# porta_OU_F.net
KiCad netlist of a schematic drawn in EAGLE
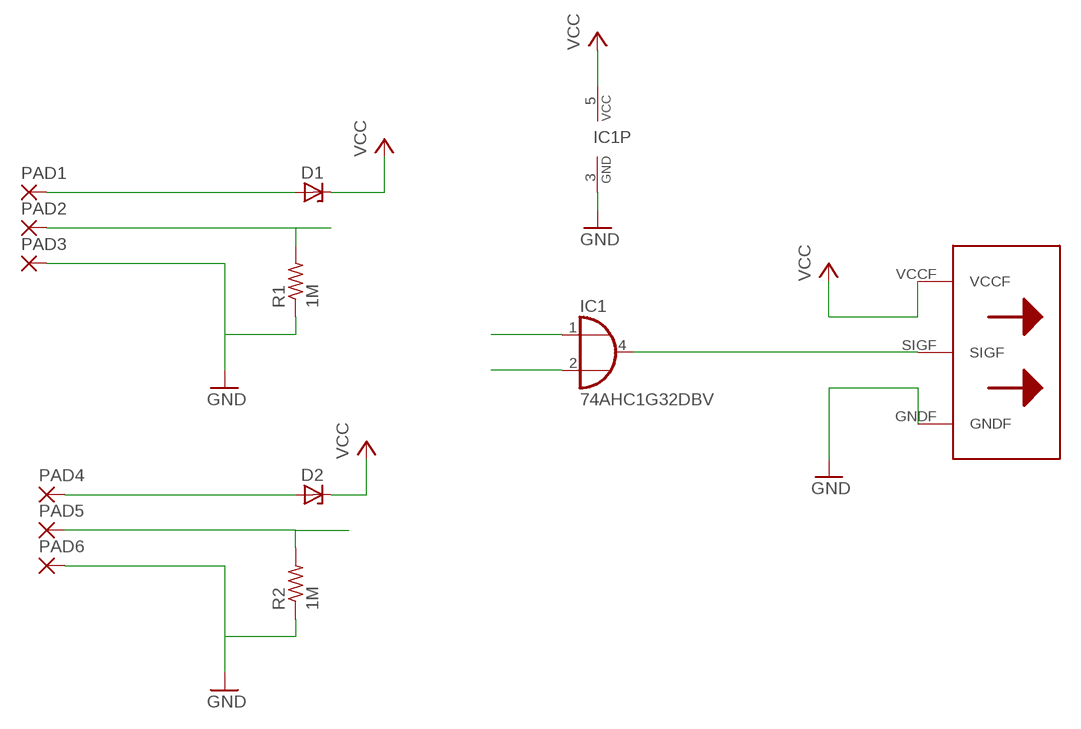
[diagram p0: schematic, sheet 1]

(export (version "E")
  (design (tool "Eeschema 10.0.6"))
  (components
    (comp (ref "D1")
      (value "ZENER-DIODESOD80C")
      (footprint "eagle-import:SOD80C")
      (libsource (lib "eagle-import") (part "ZENER-DIODESOD80C"))
    )
    (comp (ref "D2")
      (value "ZENER-DIODESOD80C")
      (footprint "eagle-import:SOD80C")
      (libsource (lib "eagle-import") (part "ZENER-DIODESOD80C"))
    )
    (comp (ref "IC1")
      (value "74AHC1G32DBV")
      (footprint "eagle-import:SOT23-5")
      (libsource (lib "eagle-import") (part "741G32DBVAHC"))
    )
    (comp (ref "PAD1")
      (value "SMD5")
      (footprint "eagle-import:SMD2,54-5,08")
      (libsource (lib "eagle-import") (part "SMD5"))
    )
    (comp (ref "PAD2")
      (value "SMD5")
      (footprint "eagle-import:SMD2,54-5,08")
      (libsource (lib "eagle-import") (part "SMD5"))
    )
    (comp (ref "PAD3")
      (value "SMD5")
      (footprint "eagle-import:SMD2,54-5,08")
      (libsource (lib "eagle-import") (part "SMD5"))
    )
    (comp (ref "PAD4")
      (value "SMD5")
      (footprint "eagle-import:SMD2,54-5,08")
      (libsource (lib "eagle-import") (part "SMD5"))
    )
    (comp (ref "PAD5")
      (value "SMD5")
      (footprint "eagle-import:SMD2,54-5,08")
      (libsource (lib "eagle-import") (part "SMD5"))
    )
    (comp (ref "PAD6")
      (value "SMD5")
      (footprint "eagle-import:SMD2,54-5,08")
      (libsource (lib "eagle-import") (part "SMD5"))
    )
    (comp (ref "R1")
      (value "1M")
      (footprint "eagle-import:M0805")
      (libsource (lib "eagle-import") (part "R-US_M0805"))
    )
    (comp (ref "R2")
      (value "1M")
      (footprint "eagle-import:M0805")
      (libsource (lib "eagle-import") (part "R-US_M0805"))
    )
    (comp (ref "U$2")
      (value "BITWIREF")
      (footprint "eagle-import:BITWIREF")
      (libsource (lib "eagle-import") (part "BITWIREF"))
    )
  )
  (nets
    (net (code "1") (name "/SIG1") (class "Default")
      (node (ref "IC1") (pin "1") (pinfunction "I0_1") (pintype "input"))
      (node (ref "PAD2") (pin "1") (pinfunction "P_1") (pintype "passive"))
      (node (ref "R1") (pin "2") (pinfunction "2_2") (pintype "passive"))
    )
    (net (code "2") (name "/SIG2") (class "Default")
      (node (ref "IC1") (pin "2") (pinfunction "I1_2") (pintype "input"))
      (node (ref "PAD5") (pin "1") (pinfunction "P_1") (pintype "passive"))
      (node (ref "R2") (pin "2") (pinfunction "2_2") (pintype "passive"))
    )
    (net (code "3") (name "GND") (class "Default")
      (node (ref "IC1") (pin "3") (pinfunction "GND_3") (pintype "power_in"))
      (node (ref "PAD3") (pin "1") (pinfunction "P_1") (pintype "passive"))
      (node (ref "PAD6") (pin "1") (pinfunction "P_1") (pintype "passive"))
      (node (ref "R1") (pin "1") (pinfunction "1_1") (pintype "passive"))
      (node (ref "R2") (pin "1") (pinfunction "1_1") (pintype "passive"))
      (node (ref "U$2") (pin "GNDF") (pinfunction "GNDF_GNDF") (pintype "bidirectional"))
    )
    (net (code "4") (name "Net-(IC1A-O)") (class "Default")
      (node (ref "IC1") (pin "4") (pinfunction "O_4") (pintype "output"))
      (node (ref "U$2") (pin "SIGF") (pinfunction "SIGF_SIGF") (pintype "bidirectional"))
    )
    (net (code "5") (name "Net-(PAD1-P)") (class "Default")
      (node (ref "D1") (pin "A") (pinfunction "A_A") (pintype "passive"))
      (node (ref "PAD1") (pin "1") (pinfunction "P_1") (pintype "passive"))
    )
    (net (code "6") (name "Net-(PAD4-P)") (class "Default")
      (node (ref "D2") (pin "A") (pinfunction "A_A") (pintype "passive"))
      (node (ref "PAD4") (pin "1") (pinfunction "P_1") (pintype "passive"))
    )
    (net (code "7") (name "VCC") (class "Default")
      (node (ref "D1") (pin "C") (pinfunction "C_C") (pintype "passive"))
      (node (ref "D2") (pin "C") (pinfunction "C_C") (pintype "passive"))
      (node (ref "IC1") (pin "5") (pinfunction "VCC_5") (pintype "power_in"))
      (node (ref "U$2") (pin "VCCF") (pinfunction "VCCF_VCCF") (pintype "bidirectional"))
    )
  )
)
